# 2016_CARTE_4_MOFSET.net
KiCad netlist of a schematic drawn in Altium Designer
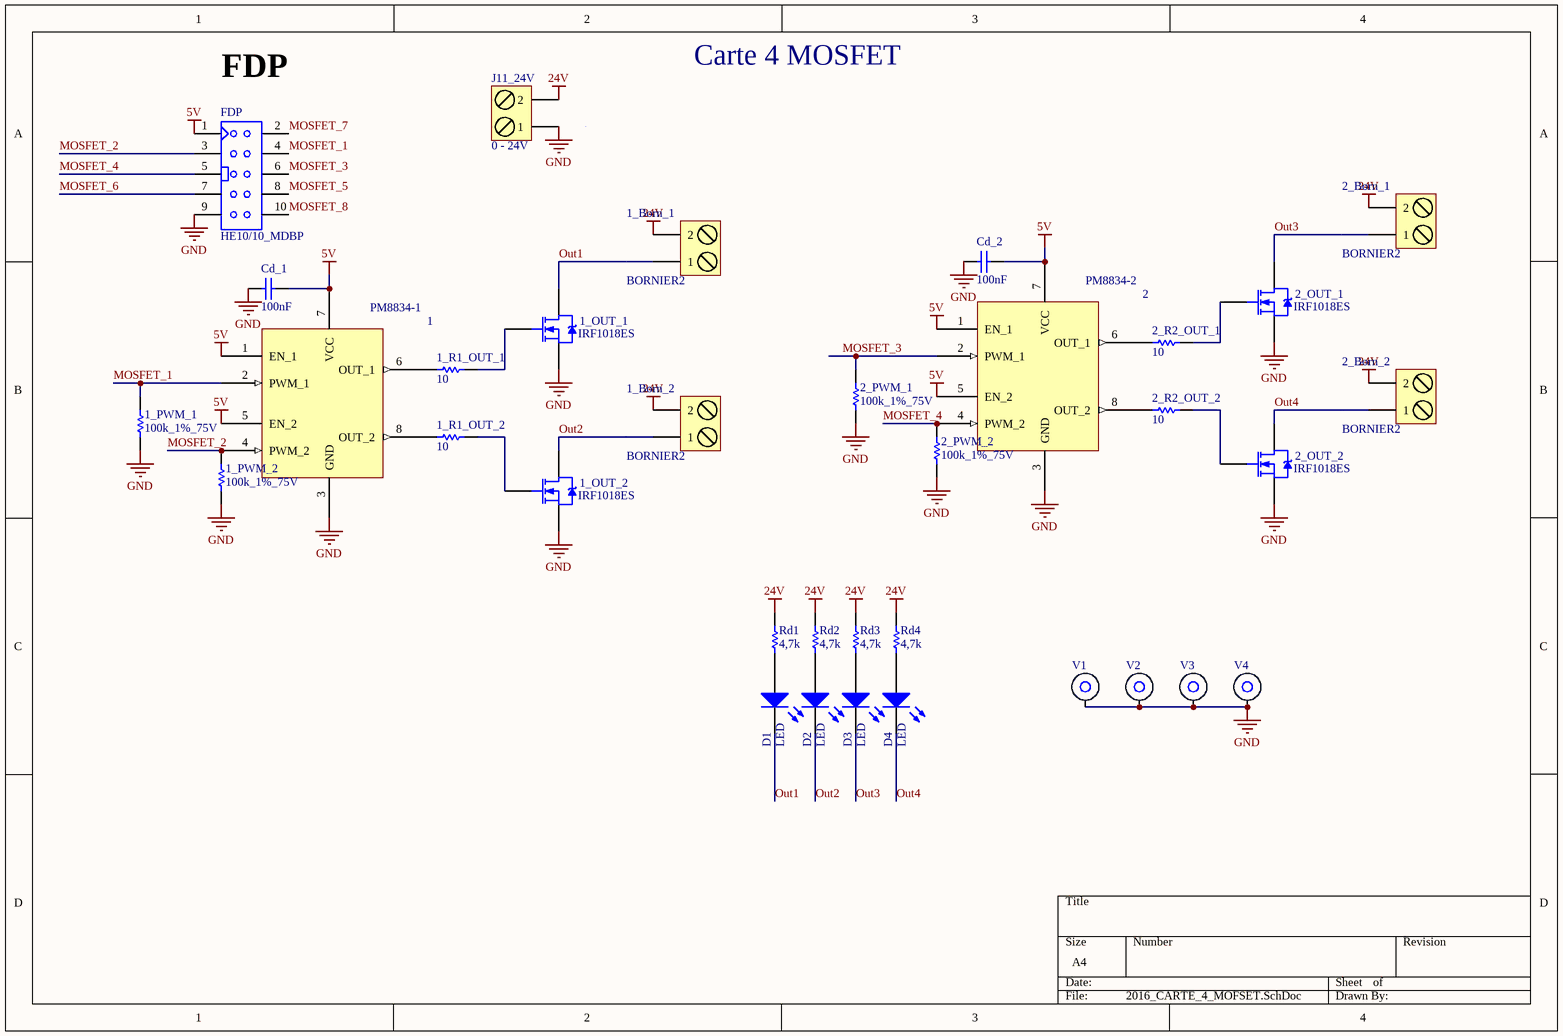
[diagram p0: 2016_CARTE_4_MOFSET.SchDoc]

(export (version "E")
  (design (tool "Eeschema 10.0.6"))
  (components
    (comp (ref "1")
      (value "PM8834-1")
      (footprint "SO8_N")
      (description "4 A dual low-side MOSFET driver")
      (libsource (lib "_ROBOT") (part "PM8834"))
    )
    (comp (ref "1_Born_1")
      (value "BORNIER2")
      (footprint "BORNIER2")
      (description "Terminal blocks, 2 pins, pitch=5mm")
      (libsource (lib "Connecteur") (part "BORNIER2"))
    )
    (comp (ref "1_Born_2")
      (value "BORNIER2")
      (footprint "BORNIER2")
      (description "Terminal blocks, 2 pins, pitch=5mm")
      (libsource (lib "Connecteur") (part "BORNIER2"))
    )
    (comp (ref "1_OUT_1")
      (value "IRF1018ES")
      (footprint "_ROBOT:D2PAK_GROS_PAD")
      (description "HEXFET N-Channel Power MOSFET")
      (fields (field (name "PUBLISHER") "Altium Limited"))
      (libsource (lib "IR Discrete MOSFET - Power") (part "IRF1010S"))
    )
    (comp (ref "1_OUT_2")
      (value "IRF1018ES")
      (footprint "D2PAK_GROS_PAD")
      (description "HEXFET N-Channel Power MOSFET")
      (fields (field (name "PUBLISHER") "Altium Limited"))
      (libsource (lib "IR Discrete MOSFET - Power") (part "IRF1010S"))
    )
    (comp (ref "1_PWM_1")
      (value "100k_1%_75V")
      (footprint "R1206_N")
      (description "Resistor")
      (fields (field (name "PUBLISHER") "Altium Limited"))
      (libsource (lib "DG_Resistance") (part "Resistor"))
    )
    (comp (ref "1_PWM_2")
      (value "100k_1%_75V")
      (footprint "R1206_N")
      (description "Resistor")
      (fields (field (name "PUBLISHER") "Altium Limited"))
      (libsource (lib "DG_Resistance") (part "Resistor"))
    )
    (comp (ref "1_R1_OUT_1")
      (value "10")
      (footprint "R1206_N")
      (description "Resistor")
      (fields (field (name "PUBLISHER") "Altium Limited"))
      (libsource (lib "_ROBOT") (part "Resistor"))
    )
    (comp (ref "1_R1_OUT_2")
      (value "10")
      (footprint "R1206_N")
      (description "Resistor")
      (fields (field (name "PUBLISHER") "Altium Limited"))
      (libsource (lib "_ROBOT") (part "Resistor"))
    )
    (comp (ref "2")
      (value "PM8834-2")
      (footprint "SO8_N")
      (description "4 A dual low-side MOSFET driver")
      (libsource (lib "_ROBOT") (part "PM8834"))
    )
    (comp (ref "2_Born_1")
      (value "BORNIER2")
      (footprint "BORNIER2")
      (description "Terminal blocks, 2 pins, pitch=5mm")
      (libsource (lib "Connecteur") (part "BORNIER2"))
    )
    (comp (ref "2_Born_2")
      (value "BORNIER2")
      (footprint "BORNIER2")
      (description "Terminal blocks, 2 pins, pitch=5mm")
      (libsource (lib "Connecteur") (part "BORNIER2"))
    )
    (comp (ref "2_OUT_1")
      (value "IRF1018ES")
      (footprint "D2PAK_GROS_PAD")
      (description "HEXFET N-Channel Power MOSFET")
      (fields (field (name "PUBLISHER") "Altium Limited"))
      (libsource (lib "IR Discrete MOSFET - Power") (part "IRF1010S"))
    )
    (comp (ref "2_OUT_2")
      (value "IRF1018ES")
      (footprint "D2PAK_GROS_PAD")
      (description "HEXFET N-Channel Power MOSFET")
      (fields (field (name "PUBLISHER") "Altium Limited"))
      (libsource (lib "IR Discrete MOSFET - Power") (part "IRF1010S"))
    )
    (comp (ref "2_PWM_1")
      (value "100k_1%_75V")
      (footprint "R1206_N")
      (description "Resistor")
      (fields (field (name "PUBLISHER") "Altium Limited"))
      (libsource (lib "DG_Resistance") (part "Resistor"))
    )
    (comp (ref "2_PWM_2")
      (value "100k_1%_75V")
      (footprint "R1206_N")
      (description "Resistor")
      (fields (field (name "PUBLISHER") "Altium Limited"))
      (libsource (lib "DG_Resistance") (part "Resistor"))
    )
    (comp (ref "2_R2_OUT_1")
      (value "10")
      (footprint "R1206_N")
      (description "Resistor")
      (fields (field (name "PUBLISHER") "Altium Limited"))
      (libsource (lib "_ROBOT") (part "Resistor"))
    )
    (comp (ref "2_R2_OUT_2")
      (value "10")
      (footprint "R1206_N")
      (description "Resistor")
      (fields (field (name "PUBLISHER") "Altium Limited"))
      (libsource (lib "_ROBOT") (part "Resistor"))
    )
    (comp (ref "Cd_1")
      (value "100nF")
      (footprint "C0805_N")
      (description "Capacitor")
      (fields (field (name "PUBLISHER") "Altium Limited"))
      (libsource (lib "_ROBOT") (part "Condensateur"))
    )
    (comp (ref "Cd_2")
      (value "100nF")
      (footprint "C0805_N")
      (description "Capacitor")
      (fields (field (name "PUBLISHER") "Altium Limited"))
      (libsource (lib "_ROBOT") (part "Condensateur"))
    )
    (comp (ref "D1")
      (value "LED")
      (footprint "LED_0805")
      (description "Typical LED")
      (fields (field (name "PUBLISHER") "Altium Limited"))
      (libsource (lib "_ROBOT") (part "LED"))
    )
    (comp (ref "D2")
      (value "LED")
      (footprint "LED_0805")
      (description "Typical LED")
      (fields (field (name "PUBLISHER") "Altium Limited"))
      (libsource (lib "_ROBOT") (part "LED"))
    )
    (comp (ref "D3")
      (value "LED")
      (footprint "LED_0805")
      (description "Typical LED")
      (fields (field (name "PUBLISHER") "Altium Limited"))
      (libsource (lib "_ROBOT") (part "LED"))
    )
    (comp (ref "D4")
      (value "LED")
      (footprint "LED_0805")
      (description "Typical LED")
      (fields (field (name "PUBLISHER") "Altium Limited"))
      (libsource (lib "_ROBOT") (part "LED"))
    )
    (comp (ref "FDP")
      (value "HE10/10_MALE_DROIT_BAS_PROFIL")
      (footprint "HE10/10_M_D_BP")
      (description "EMBASE HE10/10 MALE DROIT BAS PROFIL")
      (fields (field (name "TYPE") "HE10/10_MDBP"))
      (libsource (lib "connecteurs") (part "HE10/10_MALE_DROIT_BAS_PROFIL"))
    )
    (comp (ref "J11_24V")
      (value "0 - 24V")
      (footprint "BORNIER2_FEM_COUDE")
      (description "Terminal blocks, 2 pins, pitch=5mm")
      (libsource (lib "miniprojet") (part "BORNIER2"))
    )
    (comp (ref "Rd1")
      (value "4,7k")
      (footprint "R1206_N")
      (description "Resistor")
      (fields (field (name "PUBLISHER") "Altium Limited"))
      (libsource (lib "_ROBOT") (part "Resistor"))
    )
    (comp (ref "Rd2")
      (value "4,7k")
      (footprint "R1206_N")
      (description "Resistor")
      (fields (field (name "PUBLISHER") "Altium Limited"))
      (libsource (lib "_ROBOT") (part "Resistor"))
    )
    (comp (ref "Rd3")
      (value "4,7k")
      (footprint "R1206_N")
      (description "Resistor")
      (fields (field (name "PUBLISHER") "Altium Limited"))
      (libsource (lib "_ROBOT") (part "Resistor"))
    )
    (comp (ref "Rd4")
      (value "4,7k")
      (footprint "R1206_N")
      (description "Resistor")
      (fields (field (name "PUBLISHER") "Altium Limited"))
      (libsource (lib "_ROBOT") (part "Resistor"))
    )
    (comp (ref "V1")
      (value "Entretoise WURTH CMS")
      (footprint "ENTRETOISE_CMS")
      (description "Entretoise Wurth")
      (fields (field (name "PUBLISHER") "Damien Guitton"))
      (libsource (lib "_ROBOT") (part "Entretoise WURTH CMS"))
    )
    (comp (ref "V2")
      (value "Entretoise WURTH CMS")
      (footprint "ENTRETOISE_CMS")
      (description "Entretoise Wurth")
      (fields (field (name "PUBLISHER") "Damien Guitton"))
      (libsource (lib "_ROBOT") (part "Entretoise WURTH CMS"))
    )
    (comp (ref "V3")
      (value "Entretoise WURTH CMS")
      (footprint "ENTRETOISE_CMS")
      (description "Entretoise Wurth")
      (fields (field (name "PUBLISHER") "Damien Guitton"))
      (libsource (lib "_ROBOT") (part "Entretoise WURTH CMS"))
    )
    (comp (ref "V4")
      (value "Entretoise WURTH CMS")
      (footprint "ENTRETOISE_CMS")
      (description "Entretoise Wurth")
      (fields (field (name "PUBLISHER") "Damien Guitton"))
      (libsource (lib "_ROBOT") (part "Entretoise WURTH CMS"))
    )
  )
  (nets
    (net (code "1") (name "/MOSFET_1") (class "Default")
      (node (ref "1") (pin "2") (pinfunction "PWM_1_2") (pintype "input"))
      (node (ref "1_PWM_1") (pin "2") (pinfunction "2_2") (pintype "passive"))
      (node (ref "FDP") (pin "4") (pinfunction "4_4") (pintype "passive"))
    )
    (net (code "2") (name "/MOSFET_2") (class "Default")
      (node (ref "1") (pin "4") (pinfunction "PWM_2_4") (pintype "input"))
      (node (ref "1_PWM_2") (pin "2") (pinfunction "2_2") (pintype "passive"))
      (node (ref "FDP") (pin "3") (pinfunction "3_3") (pintype "passive"))
    )
    (net (code "3") (name "/MOSFET_3") (class "Default")
      (node (ref "2") (pin "2") (pinfunction "PWM_1_2") (pintype "input"))
      (node (ref "2_PWM_1") (pin "2") (pinfunction "2_2") (pintype "passive"))
      (node (ref "FDP") (pin "6") (pinfunction "6_6") (pintype "passive"))
    )
    (net (code "4") (name "/MOSFET_4") (class "Default")
      (node (ref "2") (pin "4") (pinfunction "PWM_2_4") (pintype "input"))
      (node (ref "2_PWM_2") (pin "2") (pinfunction "2_2") (pintype "passive"))
      (node (ref "FDP") (pin "5") (pinfunction "5_5") (pintype "passive"))
    )
    (net (code "5") (name "/MOSFET_5") (class "Default")
      (node (ref "FDP") (pin "8") (pinfunction "8_8") (pintype "passive"))
    )
    (net (code "6") (name "/MOSFET_6") (class "Default")
      (node (ref "FDP") (pin "7") (pinfunction "7_7") (pintype "passive"))
    )
    (net (code "7") (name "/MOSFET_7") (class "Default")
      (node (ref "FDP") (pin "2") (pinfunction "2_2") (pintype "passive"))
    )
    (net (code "8") (name "/MOSFET_8") (class "Default")
      (node (ref "FDP") (pin "10") (pinfunction "10_10") (pintype "passive"))
    )
    (net (code "9") (name "/Out1") (class "Default")
      (node (ref "1_Born_1") (pin "1") (pinfunction "1_1") (pintype "passive"))
      (node (ref "1_OUT_1") (pin "2") (pinfunction "D_2") (pintype "passive"))
      (node (ref "D1") (pin "2") (pinfunction "K_2") (pintype "passive"))
    )
    (net (code "10") (name "/Out2") (class "Default")
      (node (ref "1_Born_2") (pin "1") (pinfunction "1_1") (pintype "passive"))
      (node (ref "1_OUT_2") (pin "2") (pinfunction "D_2") (pintype "passive"))
      (node (ref "D2") (pin "2") (pinfunction "K_2") (pintype "passive"))
    )
    (net (code "11") (name "/Out3") (class "Default")
      (node (ref "2_Born_1") (pin "1") (pinfunction "1_1") (pintype "passive"))
      (node (ref "2_OUT_1") (pin "2") (pinfunction "D_2") (pintype "passive"))
      (node (ref "D3") (pin "2") (pinfunction "K_2") (pintype "passive"))
    )
    (net (code "12") (name "/Out4") (class "Default")
      (node (ref "2_Born_2") (pin "1") (pinfunction "1_1") (pintype "passive"))
      (node (ref "2_OUT_2") (pin "2") (pinfunction "D_2") (pintype "passive"))
      (node (ref "D4") (pin "2") (pinfunction "K_2") (pintype "passive"))
    )
    (net (code "13") (name "5V") (class "Default")
      (node (ref "1") (pin "1") (pinfunction "EN_1_1") (pintype "passive"))
      (node (ref "1") (pin "5") (pinfunction "EN_2_5") (pintype "passive"))
      (node (ref "1") (pin "7") (pinfunction "VCC_7") (pintype "power_in"))
      (node (ref "2") (pin "1") (pinfunction "EN_1_1") (pintype "passive"))
      (node (ref "2") (pin "5") (pinfunction "EN_2_5") (pintype "passive"))
      (node (ref "2") (pin "7") (pinfunction "VCC_7") (pintype "power_in"))
      (node (ref "Cd_1") (pin "2") (pinfunction "2_2") (pintype "passive"))
      (node (ref "Cd_2") (pin "2") (pinfunction "2_2") (pintype "passive"))
      (node (ref "FDP") (pin "1") (pinfunction "1_1") (pintype "passive"))
    )
    (net (code "14") (name "24V") (class "Default")
      (node (ref "1_Born_1") (pin "2") (pinfunction "2_2") (pintype "passive"))
      (node (ref "1_Born_2") (pin "2") (pinfunction "2_2") (pintype "passive"))
      (node (ref "2_Born_1") (pin "2") (pinfunction "2_2") (pintype "passive"))
      (node (ref "2_Born_2") (pin "2") (pinfunction "2_2") (pintype "passive"))
      (node (ref "J11_24V") (pin "2") (pinfunction "2_2") (pintype "passive"))
      (node (ref "Rd1") (pin "1") (pinfunction "1_1") (pintype "passive"))
      (node (ref "Rd2") (pin "1") (pinfunction "1_1") (pintype "passive"))
      (node (ref "Rd3") (pin "1") (pinfunction "1_1") (pintype "passive"))
      (node (ref "Rd4") (pin "1") (pinfunction "1_1") (pintype "passive"))
    )
    (net (code "15") (name "GND") (class "Default")
      (node (ref "1") (pin "3") (pinfunction "GND_3") (pintype "power_in"))
      (node (ref "1_OUT_1") (pin "3") (pinfunction "S_3") (pintype "passive"))
      (node (ref "1_OUT_2") (pin "3") (pinfunction "S_3") (pintype "passive"))
      (node (ref "1_PWM_1") (pin "1") (pinfunction "1_1") (pintype "passive"))
      (node (ref "1_PWM_2") (pin "1") (pinfunction "1_1") (pintype "passive"))
      (node (ref "2") (pin "3") (pinfunction "GND_3") (pintype "power_in"))
      (node (ref "2_OUT_1") (pin "3") (pinfunction "S_3") (pintype "passive"))
      (node (ref "2_OUT_2") (pin "3") (pinfunction "S_3") (pintype "passive"))
      (node (ref "2_PWM_1") (pin "1") (pinfunction "1_1") (pintype "passive"))
      (node (ref "2_PWM_2") (pin "1") (pinfunction "1_1") (pintype "passive"))
      (node (ref "Cd_1") (pin "1") (pinfunction "1_1") (pintype "passive"))
      (node (ref "Cd_2") (pin "1") (pinfunction "1_1") (pintype "passive"))
      (node (ref "FDP") (pin "9") (pinfunction "9_9") (pintype "passive"))
      (node (ref "J11_24V") (pin "1") (pinfunction "1_1") (pintype "passive"))
      (node (ref "V1") (pin "1") (pinfunction "1_1") (pintype "passive"))
      (node (ref "V2") (pin "1") (pinfunction "1_1") (pintype "passive"))
      (node (ref "V3") (pin "1") (pinfunction "1_1") (pintype "passive"))
      (node (ref "V4") (pin "1") (pinfunction "1_1") (pintype "passive"))
    )
    (net (code "16") (name "Net-(1-OUT_1)") (class "Default")
      (node (ref "1") (pin "6") (pinfunction "OUT_1_6") (pintype "output"))
      (node (ref "1_R1_OUT_1") (pin "1") (pinfunction "1_1") (pintype "passive"))
    )
    (net (code "17") (name "Net-(1-OUT_2)") (class "Default")
      (node (ref "1") (pin "8") (pinfunction "OUT_2_8") (pintype "output"))
      (node (ref "1_R1_OUT_2") (pin "1") (pinfunction "1_1") (pintype "passive"))
    )
    (net (code "18") (name "Net-(1_OUT_1-G)") (class "Default")
      (node (ref "1_OUT_1") (pin "1") (pinfunction "G_1") (pintype "passive"))
      (node (ref "1_R1_OUT_1") (pin "2") (pinfunction "2_2") (pintype "passive"))
    )
    (net (code "19") (name "Net-(1_OUT_2-G)") (class "Default")
      (node (ref "1_OUT_2") (pin "1") (pinfunction "G_1") (pintype "passive"))
      (node (ref "1_R1_OUT_2") (pin "2") (pinfunction "2_2") (pintype "passive"))
    )
    (net (code "20") (name "Net-(2-OUT_1)") (class "Default")
      (node (ref "2") (pin "6") (pinfunction "OUT_1_6") (pintype "output"))
      (node (ref "2_R2_OUT_1") (pin "1") (pinfunction "1_1") (pintype "passive"))
    )
    (net (code "21") (name "Net-(2-OUT_2)") (class "Default")
      (node (ref "2") (pin "8") (pinfunction "OUT_2_8") (pintype "output"))
      (node (ref "2_R2_OUT_2") (pin "1") (pinfunction "1_1") (pintype "passive"))
    )
    (net (code "22") (name "Net-(2_OUT_1-G)") (class "Default")
      (node (ref "2_OUT_1") (pin "1") (pinfunction "G_1") (pintype "passive"))
      (node (ref "2_R2_OUT_1") (pin "2") (pinfunction "2_2") (pintype "passive"))
    )
    (net (code "23") (name "Net-(2_OUT_2-G)") (class "Default")
      (node (ref "2_OUT_2") (pin "1") (pinfunction "G_1") (pintype "passive"))
      (node (ref "2_R2_OUT_2") (pin "2") (pinfunction "2_2") (pintype "passive"))
    )
    (net (code "24") (name "Net-(D1-A)") (class "Default")
      (node (ref "D1") (pin "1") (pinfunction "A_1") (pintype "passive"))
      (node (ref "Rd1") (pin "2") (pinfunction "2_2") (pintype "passive"))
    )
    (net (code "25") (name "Net-(D2-A)") (class "Default")
      (node (ref "D2") (pin "1") (pinfunction "A_1") (pintype "passive"))
      (node (ref "Rd2") (pin "2") (pinfunction "2_2") (pintype "passive"))
    )
    (net (code "26") (name "Net-(D3-A)") (class "Default")
      (node (ref "D3") (pin "1") (pinfunction "A_1") (pintype "passive"))
      (node (ref "Rd3") (pin "2") (pinfunction "2_2") (pintype "passive"))
    )
    (net (code "27") (name "Net-(D4-A)") (class "Default")
      (node (ref "D4") (pin "1") (pinfunction "A_1") (pintype "passive"))
      (node (ref "Rd4") (pin "2") (pinfunction "2_2") (pintype "passive"))
    )
  )
)
